# ehomeLight_doit.net
KiCad netlist of a schematic drawn in EAGLE
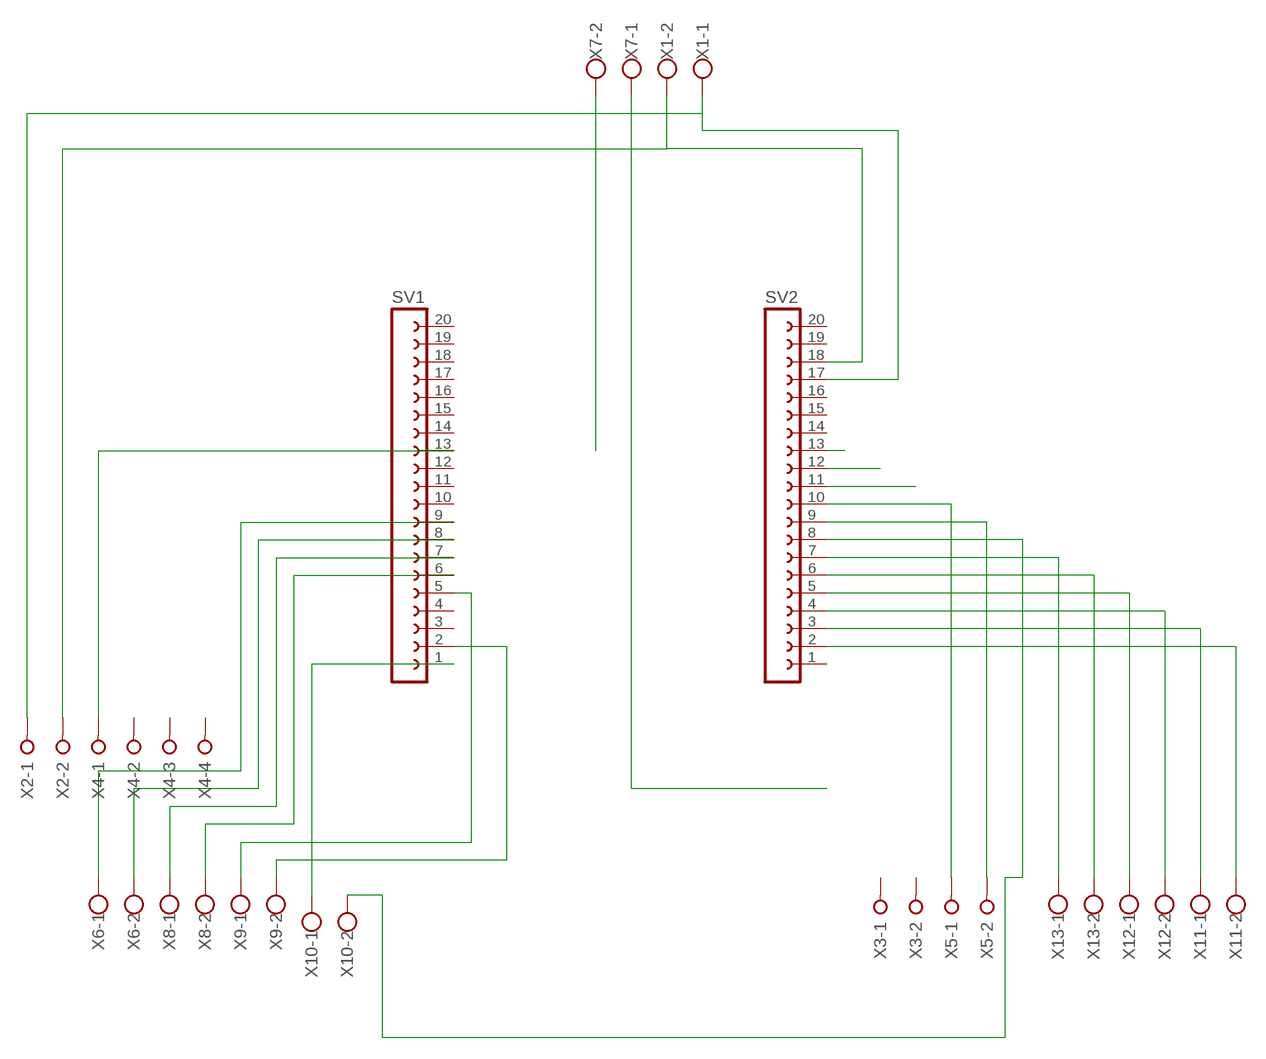
[diagram p0: schematic, sheet 1]

(export (version "E")
  (design (tool "Eeschema 10.0.6"))
  (components
    (comp (ref "SV1")
      (value "FE20-1")
      (footprint "eagle-import:FE20")
      (libsource (lib "eagle-import") (part "FE20-1"))
    )
    (comp (ref "SV2")
      (value "FE20-1")
      (footprint "eagle-import:FE20")
      (libsource (lib "eagle-import") (part "FE20-1"))
    )
    (comp (ref "X1")
      (value "W237-102")
      (footprint "eagle-import:W237-102")
      (fields (field (name "MPN") "237-102"))
      (libsource (lib "eagle-import") (part "W237-102"))
    )
    (comp (ref "X2")
      (value "W237-02P")
      (footprint "eagle-import:W237-132")
      (libsource (lib "eagle-import") (part "W237-02P"))
    )
    (comp (ref "X3")
      (value "W237-02P")
      (footprint "eagle-import:W237-132")
      (libsource (lib "eagle-import") (part "W237-02P"))
    )
    (comp (ref "X4")
      (value "W237-04P")
      (footprint "eagle-import:W237-4P")
      (libsource (lib "eagle-import") (part "W237-04P"))
    )
    (comp (ref "X5")
      (value "W237-02P")
      (footprint "eagle-import:W237-132")
      (libsource (lib "eagle-import") (part "W237-02P"))
    )
    (comp (ref "X6")
      (value "W237-102")
      (footprint "eagle-import:W237-102")
      (fields (field (name "MPN") "237-102"))
      (libsource (lib "eagle-import") (part "W237-102"))
    )
    (comp (ref "X7")
      (value "W237-102")
      (footprint "eagle-import:W237-102")
      (fields (field (name "MPN") "237-102"))
      (libsource (lib "eagle-import") (part "W237-102"))
    )
    (comp (ref "X8")
      (value "W237-102")
      (footprint "eagle-import:W237-102")
      (fields (field (name "MPN") "237-102"))
      (libsource (lib "eagle-import") (part "W237-102"))
    )
    (comp (ref "X9")
      (value "W237-102")
      (footprint "eagle-import:W237-102")
      (fields (field (name "MPN") "237-102"))
      (libsource (lib "eagle-import") (part "W237-102"))
    )
    (comp (ref "X10")
      (value "W237-102")
      (footprint "eagle-import:W237-102")
      (fields (field (name "MPN") "237-102"))
      (libsource (lib "eagle-import") (part "W237-102"))
    )
    (comp (ref "X11")
      (value "W237-102")
      (footprint "eagle-import:W237-102")
      (fields (field (name "MPN") "237-102"))
      (libsource (lib "eagle-import") (part "W237-102"))
    )
    (comp (ref "X12")
      (value "W237-102")
      (footprint "eagle-import:W237-102")
      (fields (field (name "MPN") "237-102"))
      (libsource (lib "eagle-import") (part "W237-102"))
    )
    (comp (ref "X13")
      (value "W237-102")
      (footprint "eagle-import:W237-102")
      (fields (field (name "MPN") "237-102"))
      (libsource (lib "eagle-import") (part "W237-102"))
    )
  )
  (nets
    (net (code "1") (name "Net-(X1A-KL)") (class "Default")
      (node (ref "SV2") (pin "17") (pinfunction "17_17") (pintype "passive"))
      (node (ref "X1") (pin "1") (pinfunction "KL_1") (pintype "passive"))
      (node (ref "X2") (pin "1") (pinfunction "KL_1") (pintype "passive"))
    )
    (net (code "2") (name "Net-(X1B-KL)") (class "Default")
      (node (ref "SV2") (pin "18") (pinfunction "18_18") (pintype "passive"))
      (node (ref "X1") (pin "2") (pinfunction "KL_2") (pintype "passive"))
      (node (ref "X2") (pin "2") (pinfunction "KL_2") (pintype "passive"))
    )
    (net (code "3") (name "Net-(X4A-KL)") (class "Default")
      (node (ref "SV1") (pin "13") (pinfunction "13_13") (pintype "passive"))
      (node (ref "X4") (pin "1") (pinfunction "KL_1") (pintype "passive"))
    )
    (net (code "4") (name "Net-(X5A-KL)") (class "Default")
      (node (ref "SV2") (pin "10") (pinfunction "10_10") (pintype "passive"))
      (node (ref "X5") (pin "1") (pinfunction "KL_1") (pintype "passive"))
    )
    (net (code "5") (name "Net-(X5B-KL)") (class "Default")
      (node (ref "SV2") (pin "9") (pinfunction "9_9") (pintype "passive"))
      (node (ref "X5") (pin "2") (pinfunction "KL_2") (pintype "passive"))
    )
    (net (code "6") (name "Net-(X6A-KL)") (class "Default")
      (node (ref "SV1") (pin "9") (pinfunction "9_9") (pintype "passive"))
      (node (ref "X6") (pin "1") (pinfunction "KL_1") (pintype "passive"))
    )
    (net (code "7") (name "Net-(X6B-KL)") (class "Default")
      (node (ref "SV1") (pin "8") (pinfunction "8_8") (pintype "passive"))
      (node (ref "X6") (pin "2") (pinfunction "KL_2") (pintype "passive"))
    )
    (net (code "8") (name "Net-(X8A-KL)") (class "Default")
      (node (ref "SV1") (pin "7") (pinfunction "7_7") (pintype "passive"))
      (node (ref "X8") (pin "1") (pinfunction "KL_1") (pintype "passive"))
    )
    (net (code "9") (name "Net-(X8B-KL)") (class "Default")
      (node (ref "SV1") (pin "6") (pinfunction "6_6") (pintype "passive"))
      (node (ref "X8") (pin "2") (pinfunction "KL_2") (pintype "passive"))
    )
    (net (code "10") (name "Net-(X9A-KL)") (class "Default")
      (node (ref "SV1") (pin "5") (pinfunction "5_5") (pintype "passive"))
      (node (ref "X9") (pin "1") (pinfunction "KL_1") (pintype "passive"))
    )
    (net (code "11") (name "Net-(X9B-KL)") (class "Default")
      (node (ref "SV1") (pin "2") (pinfunction "2_2") (pintype "passive"))
      (node (ref "X9") (pin "2") (pinfunction "KL_2") (pintype "passive"))
    )
    (net (code "12") (name "Net-(X10A-KL)") (class "Default")
      (node (ref "SV1") (pin "1") (pinfunction "1_1") (pintype "passive"))
      (node (ref "X10") (pin "1") (pinfunction "KL_1") (pintype "passive"))
    )
    (net (code "13") (name "Net-(X10B-KL)") (class "Default")
      (node (ref "SV2") (pin "8") (pinfunction "8_8") (pintype "passive"))
      (node (ref "X10") (pin "2") (pinfunction "KL_2") (pintype "passive"))
    )
    (net (code "14") (name "Net-(X11A-KL)") (class "Default")
      (node (ref "SV2") (pin "3") (pinfunction "3_3") (pintype "passive"))
      (node (ref "X11") (pin "1") (pinfunction "KL_1") (pintype "passive"))
    )
    (net (code "15") (name "Net-(X11B-KL)") (class "Default")
      (node (ref "SV2") (pin "2") (pinfunction "2_2") (pintype "passive"))
      (node (ref "X11") (pin "2") (pinfunction "KL_2") (pintype "passive"))
    )
    (net (code "16") (name "Net-(X12A-KL)") (class "Default")
      (node (ref "SV2") (pin "5") (pinfunction "5_5") (pintype "passive"))
      (node (ref "X12") (pin "1") (pinfunction "KL_1") (pintype "passive"))
    )
    (net (code "17") (name "Net-(X12B-KL)") (class "Default")
      (node (ref "SV2") (pin "4") (pinfunction "4_4") (pintype "passive"))
      (node (ref "X12") (pin "2") (pinfunction "KL_2") (pintype "passive"))
    )
    (net (code "18") (name "Net-(X13A-KL)") (class "Default")
      (node (ref "SV2") (pin "7") (pinfunction "7_7") (pintype "passive"))
      (node (ref "X13") (pin "1") (pinfunction "KL_1") (pintype "passive"))
    )
    (net (code "19") (name "Net-(X13B-KL)") (class "Default")
      (node (ref "SV2") (pin "6") (pinfunction "6_6") (pintype "passive"))
      (node (ref "X13") (pin "2") (pinfunction "KL_2") (pintype "passive"))
    )
    (net (code "20") (name "unconnected-(SV1-Pad3)") (class "Default")
      (node (ref "SV1") (pin "3") (pinfunction "3_3") (pintype "passive"))
    )
    (net (code "21") (name "unconnected-(SV1-Pad4)") (class "Default")
      (node (ref "SV1") (pin "4") (pinfunction "4_4") (pintype "passive"))
    )
    (net (code "22") (name "unconnected-(SV1-Pad10)") (class "Default")
      (node (ref "SV1") (pin "10") (pinfunction "10_10") (pintype "passive"))
    )
    (net (code "23") (name "unconnected-(SV1-Pad11)") (class "Default")
      (node (ref "SV1") (pin "11") (pinfunction "11_11") (pintype "passive"))
    )
    (net (code "24") (name "unconnected-(SV1-Pad12)") (class "Default")
      (node (ref "SV1") (pin "12") (pinfunction "12_12") (pintype "passive"))
    )
    (net (code "25") (name "unconnected-(SV1-Pad14)") (class "Default")
      (node (ref "SV1") (pin "14") (pinfunction "14_14") (pintype "passive"))
    )
    (net (code "26") (name "unconnected-(SV1-Pad15)") (class "Default")
      (node (ref "SV1") (pin "15") (pinfunction "15_15") (pintype "passive"))
    )
    (net (code "27") (name "unconnected-(SV1-Pad16)") (class "Default")
      (node (ref "SV1") (pin "16") (pinfunction "16_16") (pintype "passive"))
    )
    (net (code "28") (name "unconnected-(SV1-Pad17)") (class "Default")
      (node (ref "SV1") (pin "17") (pinfunction "17_17") (pintype "passive"))
    )
    (net (code "29") (name "unconnected-(SV1-Pad18)") (class "Default")
      (node (ref "SV1") (pin "18") (pinfunction "18_18") (pintype "passive"))
    )
    (net (code "30") (name "unconnected-(SV1-Pad19)") (class "Default")
      (node (ref "SV1") (pin "19") (pinfunction "19_19") (pintype "passive"))
    )
    (net (code "31") (name "unconnected-(SV1-Pad20)") (class "Default")
      (node (ref "SV1") (pin "20") (pinfunction "20_20") (pintype "passive"))
    )
    (net (code "32") (name "unconnected-(SV2-Pad1)") (class "Default")
      (node (ref "SV2") (pin "1") (pinfunction "1_1") (pintype "passive"))
    )
    (net (code "33") (name "unconnected-(SV2-Pad11)") (class "Default")
      (node (ref "SV2") (pin "11") (pinfunction "11_11") (pintype "passive"))
    )
    (net (code "34") (name "unconnected-(SV2-Pad12)") (class "Default")
      (node (ref "SV2") (pin "12") (pinfunction "12_12") (pintype "passive"))
    )
    (net (code "35") (name "unconnected-(SV2-Pad13)") (class "Default")
      (node (ref "SV2") (pin "13") (pinfunction "13_13") (pintype "passive"))
    )
    (net (code "36") (name "unconnected-(SV2-Pad14)") (class "Default")
      (node (ref "SV2") (pin "14") (pinfunction "14_14") (pintype "passive"))
    )
    (net (code "37") (name "unconnected-(SV2-Pad15)") (class "Default")
      (node (ref "SV2") (pin "15") (pinfunction "15_15") (pintype "passive"))
    )
    (net (code "38") (name "unconnected-(SV2-Pad16)") (class "Default")
      (node (ref "SV2") (pin "16") (pinfunction "16_16") (pintype "passive"))
    )
    (net (code "39") (name "unconnected-(SV2-Pad19)") (class "Default")
      (node (ref "SV2") (pin "19") (pinfunction "19_19") (pintype "passive"))
    )
    (net (code "40") (name "unconnected-(SV2-Pad20)") (class "Default")
      (node (ref "SV2") (pin "20") (pinfunction "20_20") (pintype "passive"))
    )
    (net (code "41") (name "unconnected-(X3A-KL-Pad1)") (class "Default")
      (node (ref "X3") (pin "1") (pinfunction "KL_1") (pintype "passive"))
    )
    (net (code "42") (name "unconnected-(X3B-KL-Pad2)") (class "Default")
      (node (ref "X3") (pin "2") (pinfunction "KL_2") (pintype "passive"))
    )
    (net (code "43") (name "unconnected-(X4B-KL-Pad2)") (class "Default")
      (node (ref "X4") (pin "2") (pinfunction "KL_2") (pintype "passive"))
    )
    (net (code "44") (name "unconnected-(X4C-KL-Pad3)") (class "Default")
      (node (ref "X4") (pin "3") (pinfunction "KL_3") (pintype "passive"))
    )
    (net (code "45") (name "unconnected-(X4D-KL-Pad4)") (class "Default")
      (node (ref "X4") (pin "4") (pinfunction "KL_4") (pintype "passive"))
    )
    (net (code "46") (name "unconnected-(X7A-KL-Pad1)") (class "Default")
      (node (ref "X7") (pin "1") (pinfunction "KL_1") (pintype "passive"))
    )
    (net (code "47") (name "unconnected-(X7B-KL-Pad2)") (class "Default")
      (node (ref "X7") (pin "2") (pinfunction "KL_2") (pintype "passive"))
    )
  )
)
